# PowerSensingBoard.net
KiCad netlist of a schematic drawn in EAGLE
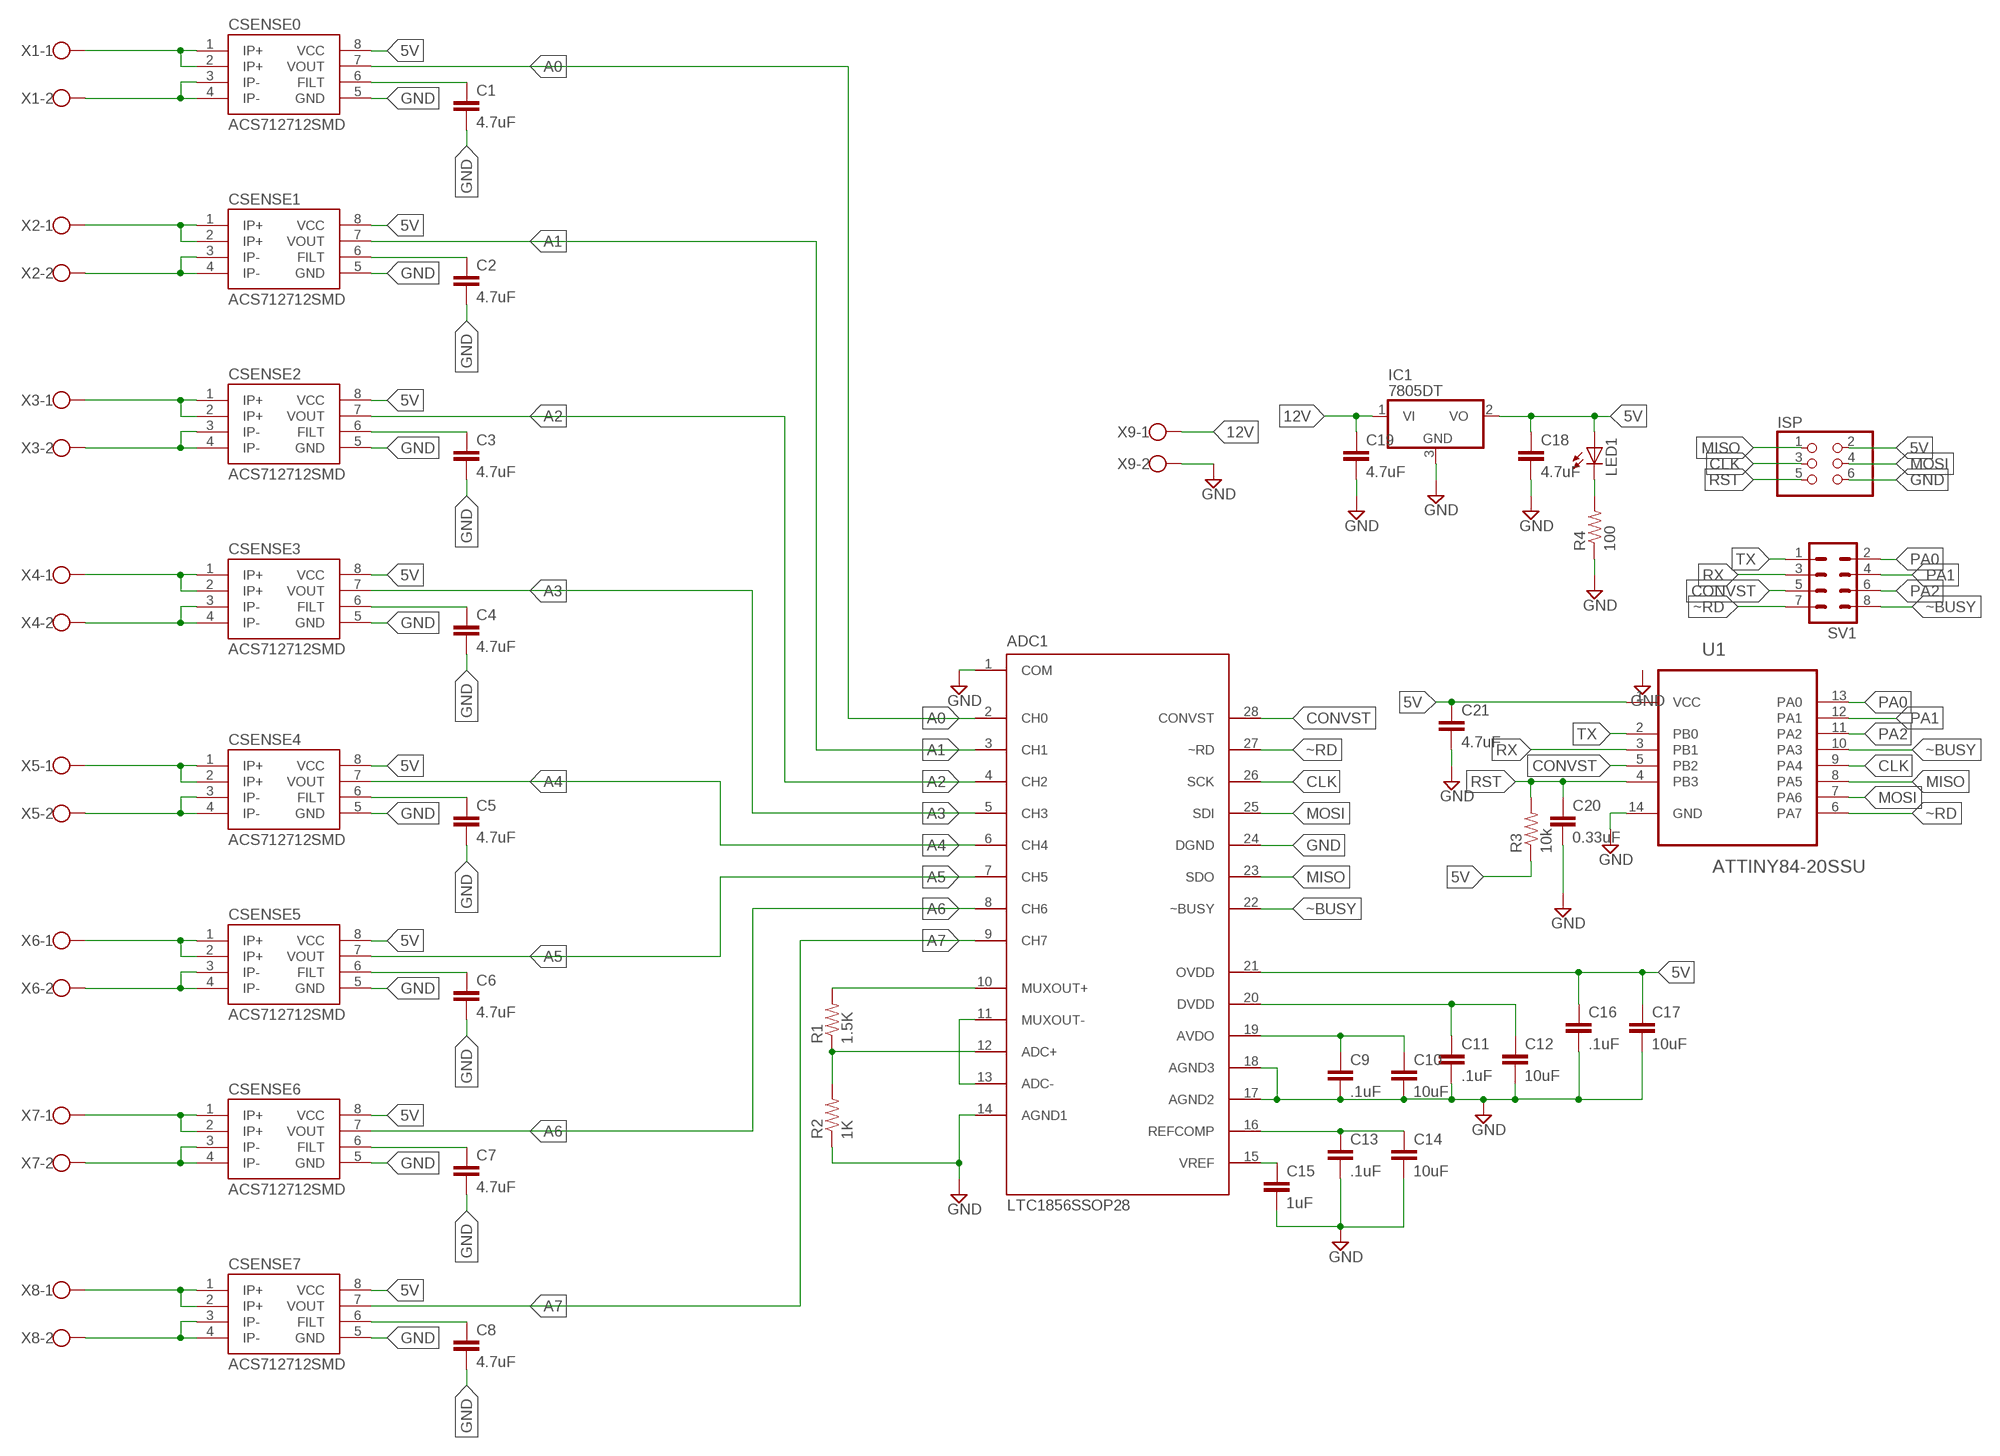
[diagram p0: schematic, sheet 1]

(export (version "E")
  (design (tool "Eeschema 10.0.6"))
  (components
    (comp (ref "ADC1")
      (value "LTC1856SSOP28")
      (footprint "eagle-import:SSOP-28")
      (libsource (lib "eagle-import") (part "LTC1856SSOP28"))
    )
    (comp (ref "C1")
      (value "4.7uF")
      (footprint "eagle-import:0603-CAP")
      (libsource (lib "eagle-import") (part "4.7UF-6.3V-10%(0603)0603"))
    )
    (comp (ref "C2")
      (value "4.7uF")
      (footprint "eagle-import:0603-CAP")
      (libsource (lib "eagle-import") (part "4.7UF-6.3V-10%(0603)0603"))
    )
    (comp (ref "C3")
      (value "4.7uF")
      (footprint "eagle-import:0603-CAP")
      (libsource (lib "eagle-import") (part "4.7UF-6.3V-10%(0603)0603"))
    )
    (comp (ref "C4")
      (value "4.7uF")
      (footprint "eagle-import:0603-CAP")
      (libsource (lib "eagle-import") (part "4.7UF-6.3V-10%(0603)0603"))
    )
    (comp (ref "C5")
      (value "4.7uF")
      (footprint "eagle-import:0603-CAP")
      (libsource (lib "eagle-import") (part "4.7UF-6.3V-10%(0603)0603"))
    )
    (comp (ref "C6")
      (value "4.7uF")
      (footprint "eagle-import:0603-CAP")
      (libsource (lib "eagle-import") (part "4.7UF-6.3V-10%(0603)0603"))
    )
    (comp (ref "C7")
      (value "4.7uF")
      (footprint "eagle-import:0603-CAP")
      (libsource (lib "eagle-import") (part "4.7UF-6.3V-10%(0603)0603"))
    )
    (comp (ref "C8")
      (value "4.7uF")
      (footprint "eagle-import:0603-CAP")
      (libsource (lib "eagle-import") (part "4.7UF-6.3V-10%(0603)0603"))
    )
    (comp (ref "C9")
      (value ".1uF")
      (footprint "eagle-import:0603-CAP")
      (libsource (lib "eagle-import") (part "4.7UF-6.3V-10%(0603)0603"))
    )
    (comp (ref "C10")
      (value "10uF")
      (footprint "eagle-import:0603-CAP")
      (libsource (lib "eagle-import") (part "4.7UF-6.3V-10%(0603)0603"))
    )
    (comp (ref "C11")
      (value ".1uF")
      (footprint "eagle-import:0603-CAP")
      (libsource (lib "eagle-import") (part "4.7UF-6.3V-10%(0603)0603"))
    )
    (comp (ref "C12")
      (value "10uF")
      (footprint "eagle-import:0603-CAP")
      (libsource (lib "eagle-import") (part "4.7UF-6.3V-10%(0603)0603"))
    )
    (comp (ref "C13")
      (value ".1uF")
      (footprint "eagle-import:0603-CAP")
      (libsource (lib "eagle-import") (part "4.7UF-6.3V-10%(0603)0603"))
    )
    (comp (ref "C14")
      (value "10uF")
      (footprint "eagle-import:0603-CAP")
      (libsource (lib "eagle-import") (part "4.7UF-6.3V-10%(0603)0603"))
    )
    (comp (ref "C15")
      (value "1uF")
      (footprint "eagle-import:0603-CAP")
      (libsource (lib "eagle-import") (part "4.7UF-6.3V-10%(0603)0603"))
    )
    (comp (ref "C16")
      (value ".1uF")
      (footprint "eagle-import:0603-CAP")
      (libsource (lib "eagle-import") (part "4.7UF-6.3V-10%(0603)0603"))
    )
    (comp (ref "C17")
      (value "10uF")
      (footprint "eagle-import:0603-CAP")
      (libsource (lib "eagle-import") (part "4.7UF-6.3V-10%(0603)0603"))
    )
    (comp (ref "C18")
      (value "4.7uF")
      (footprint "eagle-import:0603-CAP")
      (libsource (lib "eagle-import") (part "4.7UF-6.3V-10%(0603)0603"))
    )
    (comp (ref "C19")
      (value "4.7uF")
      (footprint "eagle-import:0603-CAP")
      (libsource (lib "eagle-import") (part "4.7UF-6.3V-10%(0603)0603"))
    )
    (comp (ref "C20")
      (value "0.33uF")
      (footprint "eagle-import:0805-CAP")
      (libsource (lib "eagle-import") (part "0.33UF-50V-10%(0805)"))
    )
    (comp (ref "C21")
      (value "4.7uF")
      (footprint "eagle-import:0603-CAP")
      (libsource (lib "eagle-import") (part "4.7UF-6.3V-10%(0603)0603"))
    )
    (comp (ref "CSENSE0")
      (value "ACS712712SMD")
      (footprint "eagle-import:SO08")
      (libsource (lib "eagle-import") (part "ACS712712SMD"))
    )
    (comp (ref "CSENSE1")
      (value "ACS712712SMD")
      (footprint "eagle-import:SO08")
      (libsource (lib "eagle-import") (part "ACS712712SMD"))
    )
    (comp (ref "CSENSE2")
      (value "ACS712712SMD")
      (footprint "eagle-import:SO08")
      (libsource (lib "eagle-import") (part "ACS712712SMD"))
    )
    (comp (ref "CSENSE3")
      (value "ACS712712SMD")
      (footprint "eagle-import:SO08")
      (libsource (lib "eagle-import") (part "ACS712712SMD"))
    )
    (comp (ref "CSENSE4")
      (value "ACS712712SMD")
      (footprint "eagle-import:SO08")
      (libsource (lib "eagle-import") (part "ACS712712SMD"))
    )
    (comp (ref "CSENSE5")
      (value "ACS712712SMD")
      (footprint "eagle-import:SO08")
      (libsource (lib "eagle-import") (part "ACS712712SMD"))
    )
    (comp (ref "CSENSE6")
      (value "ACS712712SMD")
      (footprint "eagle-import:SO08")
      (libsource (lib "eagle-import") (part "ACS712712SMD"))
    )
    (comp (ref "CSENSE7")
      (value "ACS712712SMD")
      (footprint "eagle-import:SO08")
      (libsource (lib "eagle-import") (part "ACS712712SMD"))
    )
    (comp (ref "IC1")
      (value "7805DT")
      (footprint "eagle-import:TO252")
      (libsource (lib "eagle-import") (part "78DT05"))
    )
    (comp (ref "ISP")
      (value "PINHD-2X3")
      (footprint "eagle-import:2X03")
      (libsource (lib "eagle-import") (part "PINHD-2X3"))
    )
    (comp (ref "LED1")
      (value "LEDCHIP-LED0805")
      (footprint "eagle-import:CHIP-LED0805")
      (libsource (lib "eagle-import") (part "LEDCHIP-LED0805"))
    )
    (comp (ref "R1")
      (value "1.5K")
      (footprint "eagle-import:0603-RES")
      (libsource (lib "eagle-import") (part "1KOHM-1/10W-1%(0603)"))
    )
    (comp (ref "R2")
      (value "1K")
      (footprint "eagle-import:0603-RES")
      (libsource (lib "eagle-import") (part "1KOHM-1/10W-1%(0603)"))
    )
    (comp (ref "R3")
      (value "10k")
      (footprint "eagle-import:0805")
      (libsource (lib "eagle-import") (part "0.3OHM-1/8W-1%(0805)"))
    )
    (comp (ref "R4")
      (value "100")
      (footprint "eagle-import:0603-RES")
      (libsource (lib "eagle-import") (part "1KOHM-1/10W-1%(0603)"))
    )
    (comp (ref "SV1")
      (value "MA04-2")
      (footprint "eagle-import:MA04-2")
      (libsource (lib "eagle-import") (part "MA04-2"))
    )
    (comp (ref "U1")
      (value "ATTINY84-20SSU")
      (footprint "eagle-import:SOIC127P600X175-14N")
      (libsource (lib "eagle-import") (part "ATTINY84-20SSU"))
    )
    (comp (ref "X1")
      (value "W237-102")
      (footprint "eagle-import:W237-102")
      (fields (field (name "MPN") "237-102"))
      (libsource (lib "eagle-import") (part "W237-102"))
    )
    (comp (ref "X2")
      (value "W237-102")
      (footprint "eagle-import:W237-102")
      (fields (field (name "MPN") "237-102"))
      (libsource (lib "eagle-import") (part "W237-102"))
    )
    (comp (ref "X3")
      (value "W237-102")
      (footprint "eagle-import:W237-102")
      (fields (field (name "MPN") "237-102"))
      (libsource (lib "eagle-import") (part "W237-102"))
    )
    (comp (ref "X4")
      (value "W237-102")
      (footprint "eagle-import:W237-102")
      (fields (field (name "MPN") "237-102"))
      (libsource (lib "eagle-import") (part "W237-102"))
    )
    (comp (ref "X5")
      (value "W237-102")
      (footprint "eagle-import:W237-102")
      (fields (field (name "MPN") "237-102"))
      (libsource (lib "eagle-import") (part "W237-102"))
    )
    (comp (ref "X6")
      (value "W237-102")
      (footprint "eagle-import:W237-102")
      (fields (field (name "MPN") "237-102"))
      (libsource (lib "eagle-import") (part "W237-102"))
    )
    (comp (ref "X7")
      (value "W237-102")
      (footprint "eagle-import:W237-102")
      (fields (field (name "MPN") "237-102"))
      (libsource (lib "eagle-import") (part "W237-102"))
    )
    (comp (ref "X8")
      (value "W237-102")
      (footprint "eagle-import:W237-102")
      (fields (field (name "MPN") "237-102"))
      (libsource (lib "eagle-import") (part "W237-102"))
    )
    (comp (ref "X9")
      (value "W237-102")
      (footprint "eagle-import:W237-102")
      (fields (field (name "MPN") "237-102"))
      (libsource (lib "eagle-import") (part "W237-102"))
    )
  )
  (nets
    (net (code "1") (name "/~{BUSY}") (class "Default")
      (node (ref "ADC1") (pin "22") (pinfunction "~{BUSY}_22") (pintype "bidirectional"))
      (node (ref "SV1") (pin "8") (pinfunction "8_8") (pintype "passive"))
      (node (ref "U1") (pin "10") (pinfunction "PA3_10") (pintype "bidirectional"))
    )
    (net (code "2") (name "/~{RD}") (class "Default")
      (node (ref "ADC1") (pin "27") (pinfunction "~{RD}_27") (pintype "bidirectional"))
      (node (ref "SV1") (pin "7") (pinfunction "7_7") (pintype "passive"))
      (node (ref "U1") (pin "6") (pinfunction "PA7_6") (pintype "bidirectional"))
    )
    (net (code "3") (name "5V") (class "Default")
      (node (ref "ADC1") (pin "21") (pinfunction "OVDD_21") (pintype "bidirectional"))
      (node (ref "C16") (pin "1") (pinfunction "1_1") (pintype "passive"))
      (node (ref "C17") (pin "1") (pinfunction "1_1") (pintype "passive"))
      (node (ref "C18") (pin "1") (pinfunction "1_1") (pintype "passive"))
      (node (ref "C21") (pin "1") (pinfunction "1_1") (pintype "passive"))
      (node (ref "CSENSE0") (pin "8") (pinfunction "VCC_8") (pintype "bidirectional"))
      (node (ref "CSENSE1") (pin "8") (pinfunction "VCC_8") (pintype "bidirectional"))
      (node (ref "CSENSE2") (pin "8") (pinfunction "VCC_8") (pintype "bidirectional"))
      (node (ref "CSENSE3") (pin "8") (pinfunction "VCC_8") (pintype "bidirectional"))
      (node (ref "CSENSE4") (pin "8") (pinfunction "VCC_8") (pintype "bidirectional"))
      (node (ref "CSENSE5") (pin "8") (pinfunction "VCC_8") (pintype "bidirectional"))
      (node (ref "CSENSE6") (pin "8") (pinfunction "VCC_8") (pintype "bidirectional"))
      (node (ref "CSENSE7") (pin "8") (pinfunction "VCC_8") (pintype "bidirectional"))
      (node (ref "IC1") (pin "2") (pinfunction "VO_2") (pintype "passive"))
      (node (ref "ISP") (pin "2") (pinfunction "2_2") (pintype "passive"))
      (node (ref "LED1") (pin "A") (pinfunction "A_A") (pintype "passive"))
      (node (ref "R3") (pin "1") (pinfunction "1_1") (pintype "passive"))
      (node (ref "U1") (pin "1") (pinfunction "VCC_1") (pintype "power_in"))
    )
    (net (code "4") (name "12V") (class "Default")
      (node (ref "C19") (pin "1") (pinfunction "1_1") (pintype "passive"))
      (node (ref "IC1") (pin "1") (pinfunction "VI_1") (pintype "input"))
      (node (ref "X9") (pin "1") (pinfunction "KL_1") (pintype "passive"))
    )
    (net (code "5") (name "A0") (class "Default")
      (node (ref "ADC1") (pin "2") (pinfunction "CH0_2") (pintype "bidirectional"))
      (node (ref "CSENSE0") (pin "7") (pinfunction "VOUT_7") (pintype "bidirectional"))
    )
    (net (code "6") (name "A1") (class "Default")
      (node (ref "ADC1") (pin "3") (pinfunction "CH1_3") (pintype "bidirectional"))
      (node (ref "CSENSE1") (pin "7") (pinfunction "VOUT_7") (pintype "bidirectional"))
    )
    (net (code "7") (name "A2") (class "Default")
      (node (ref "ADC1") (pin "4") (pinfunction "CH2_4") (pintype "bidirectional"))
      (node (ref "CSENSE2") (pin "7") (pinfunction "VOUT_7") (pintype "bidirectional"))
    )
    (net (code "8") (name "A3") (class "Default")
      (node (ref "ADC1") (pin "5") (pinfunction "CH3_5") (pintype "bidirectional"))
      (node (ref "CSENSE3") (pin "7") (pinfunction "VOUT_7") (pintype "bidirectional"))
    )
    (net (code "9") (name "A4") (class "Default")
      (node (ref "ADC1") (pin "6") (pinfunction "CH4_6") (pintype "bidirectional"))
      (node (ref "CSENSE4") (pin "7") (pinfunction "VOUT_7") (pintype "bidirectional"))
    )
    (net (code "10") (name "A5") (class "Default")
      (node (ref "ADC1") (pin "7") (pinfunction "CH5_7") (pintype "bidirectional"))
      (node (ref "CSENSE5") (pin "7") (pinfunction "VOUT_7") (pintype "bidirectional"))
    )
    (net (code "11") (name "A6") (class "Default")
      (node (ref "ADC1") (pin "8") (pinfunction "CH6_8") (pintype "bidirectional"))
      (node (ref "CSENSE6") (pin "7") (pinfunction "VOUT_7") (pintype "bidirectional"))
    )
    (net (code "12") (name "A7") (class "Default")
      (node (ref "ADC1") (pin "9") (pinfunction "CH7_9") (pintype "bidirectional"))
      (node (ref "CSENSE7") (pin "7") (pinfunction "VOUT_7") (pintype "bidirectional"))
    )
    (net (code "13") (name "CLK") (class "Default")
      (node (ref "ADC1") (pin "26") (pinfunction "SCK_26") (pintype "bidirectional"))
      (node (ref "ISP") (pin "3") (pinfunction "3_3") (pintype "passive"))
      (node (ref "U1") (pin "9") (pinfunction "PA4_9") (pintype "bidirectional"))
    )
    (net (code "14") (name "CONVST") (class "Default")
      (node (ref "ADC1") (pin "28") (pinfunction "CONVST_28") (pintype "bidirectional"))
      (node (ref "SV1") (pin "5") (pinfunction "5_5") (pintype "passive"))
      (node (ref "U1") (pin "5") (pinfunction "PB2_5") (pintype "bidirectional"))
    )
    (net (code "15") (name "GND") (class "Default")
      (node (ref "ADC1") (pin "1") (pinfunction "COM_1") (pintype "bidirectional"))
      (node (ref "ADC1") (pin "14") (pinfunction "AGND1_14") (pintype "bidirectional"))
      (node (ref "ADC1") (pin "17") (pinfunction "AGND2_17") (pintype "bidirectional"))
      (node (ref "ADC1") (pin "18") (pinfunction "AGND3_18") (pintype "bidirectional"))
      (node (ref "ADC1") (pin "24") (pinfunction "DGND_24") (pintype "bidirectional"))
      (node (ref "C1") (pin "2") (pinfunction "2_2") (pintype "passive"))
      (node (ref "C10") (pin "2") (pinfunction "2_2") (pintype "passive"))
      (node (ref "C11") (pin "2") (pinfunction "2_2") (pintype "passive"))
      (node (ref "C12") (pin "2") (pinfunction "2_2") (pintype "passive"))
      (node (ref "C13") (pin "2") (pinfunction "2_2") (pintype "passive"))
      (node (ref "C14") (pin "2") (pinfunction "2_2") (pintype "passive"))
      (node (ref "C15") (pin "2") (pinfunction "2_2") (pintype "passive"))
      (node (ref "C16") (pin "2") (pinfunction "2_2") (pintype "passive"))
      (node (ref "C17") (pin "2") (pinfunction "2_2") (pintype "passive"))
      (node (ref "C18") (pin "2") (pinfunction "2_2") (pintype "passive"))
      (node (ref "C19") (pin "2") (pinfunction "2_2") (pintype "passive"))
      (node (ref "C2") (pin "2") (pinfunction "2_2") (pintype "passive"))
      (node (ref "C20") (pin "2") (pinfunction "2_2") (pintype "passive"))
      (node (ref "C21") (pin "2") (pinfunction "2_2") (pintype "passive"))
      (node (ref "C3") (pin "2") (pinfunction "2_2") (pintype "passive"))
      (node (ref "C4") (pin "2") (pinfunction "2_2") (pintype "passive"))
      (node (ref "C5") (pin "2") (pinfunction "2_2") (pintype "passive"))
      (node (ref "C6") (pin "2") (pinfunction "2_2") (pintype "passive"))
      (node (ref "C7") (pin "2") (pinfunction "2_2") (pintype "passive"))
      (node (ref "C8") (pin "2") (pinfunction "2_2") (pintype "passive"))
      (node (ref "C9") (pin "2") (pinfunction "2_2") (pintype "passive"))
      (node (ref "CSENSE0") (pin "5") (pinfunction "GND_5") (pintype "bidirectional"))
      (node (ref "CSENSE1") (pin "5") (pinfunction "GND_5") (pintype "bidirectional"))
      (node (ref "CSENSE2") (pin "5") (pinfunction "GND_5") (pintype "bidirectional"))
      (node (ref "CSENSE3") (pin "5") (pinfunction "GND_5") (pintype "bidirectional"))
      (node (ref "CSENSE4") (pin "5") (pinfunction "GND_5") (pintype "bidirectional"))
      (node (ref "CSENSE5") (pin "5") (pinfunction "GND_5") (pintype "bidirectional"))
      (node (ref "CSENSE6") (pin "5") (pinfunction "GND_5") (pintype "bidirectional"))
      (node (ref "CSENSE7") (pin "5") (pinfunction "GND_5") (pintype "bidirectional"))
      (node (ref "IC1") (pin "3") (pinfunction "GND_3") (pintype "passive"))
      (node (ref "ISP") (pin "6") (pinfunction "6_6") (pintype "passive"))
      (node (ref "R2") (pin "1") (pinfunction "1_1") (pintype "passive"))
      (node (ref "R4") (pin "1") (pinfunction "1_1") (pintype "passive"))
      (node (ref "U1") (pin "14") (pinfunction "GND_14") (pintype "passive"))
      (node (ref "X9") (pin "2") (pinfunction "KL_2") (pintype "passive"))
    )
    (net (code "16") (name "MISO") (class "Default")
      (node (ref "ADC1") (pin "23") (pinfunction "SDO_23") (pintype "bidirectional"))
      (node (ref "ISP") (pin "1") (pinfunction "1_1") (pintype "passive"))
      (node (ref "U1") (pin "8") (pinfunction "PA5_8") (pintype "bidirectional"))
    )
    (net (code "17") (name "MOSI") (class "Default")
      (node (ref "ADC1") (pin "25") (pinfunction "SDI_25") (pintype "bidirectional"))
      (node (ref "ISP") (pin "4") (pinfunction "4_4") (pintype "passive"))
      (node (ref "U1") (pin "7") (pinfunction "PA6_7") (pintype "bidirectional"))
    )
    (net (code "18") (name "Net-(ADC1-ADC+)") (class "Default")
      (node (ref "ADC1") (pin "12") (pinfunction "ADC+_12") (pintype "bidirectional"))
      (node (ref "R1") (pin "1") (pinfunction "1_1") (pintype "passive"))
      (node (ref "R2") (pin "2") (pinfunction "2_2") (pintype "passive"))
    )
    (net (code "19") (name "Net-(ADC1-ADC-)") (class "Default")
      (node (ref "ADC1") (pin "11") (pinfunction "MUXOUT-_11") (pintype "bidirectional"))
      (node (ref "ADC1") (pin "13") (pinfunction "ADC-_13") (pintype "bidirectional"))
    )
    (net (code "20") (name "Net-(ADC1-AVDO)") (class "Default")
      (node (ref "ADC1") (pin "19") (pinfunction "AVDO_19") (pintype "bidirectional"))
      (node (ref "C10") (pin "1") (pinfunction "1_1") (pintype "passive"))
      (node (ref "C9") (pin "1") (pinfunction "1_1") (pintype "passive"))
    )
    (net (code "21") (name "Net-(ADC1-DVDD)") (class "Default")
      (node (ref "ADC1") (pin "20") (pinfunction "DVDD_20") (pintype "bidirectional"))
      (node (ref "C11") (pin "1") (pinfunction "1_1") (pintype "passive"))
      (node (ref "C12") (pin "1") (pinfunction "1_1") (pintype "passive"))
    )
    (net (code "22") (name "Net-(ADC1-MUXOUT+)") (class "Default")
      (node (ref "ADC1") (pin "10") (pinfunction "MUXOUT+_10") (pintype "bidirectional"))
      (node (ref "R1") (pin "2") (pinfunction "2_2") (pintype "passive"))
    )
    (net (code "23") (name "Net-(ADC1-REFCOMP)") (class "Default")
      (node (ref "ADC1") (pin "16") (pinfunction "REFCOMP_16") (pintype "bidirectional"))
      (node (ref "C13") (pin "1") (pinfunction "1_1") (pintype "passive"))
      (node (ref "C14") (pin "1") (pinfunction "1_1") (pintype "passive"))
    )
    (net (code "24") (name "Net-(ADC1-VREF)") (class "Default")
      (node (ref "ADC1") (pin "15") (pinfunction "VREF_15") (pintype "bidirectional"))
      (node (ref "C15") (pin "1") (pinfunction "1_1") (pintype "passive"))
    )
    (net (code "25") (name "Net-(CSENSE0-FILT)") (class "Default")
      (node (ref "C1") (pin "1") (pinfunction "1_1") (pintype "passive"))
      (node (ref "CSENSE0") (pin "6") (pinfunction "FILT_6") (pintype "bidirectional"))
    )
    (net (code "26") (name "Net-(CSENSE1-FILT)") (class "Default")
      (node (ref "C2") (pin "1") (pinfunction "1_1") (pintype "passive"))
      (node (ref "CSENSE1") (pin "6") (pinfunction "FILT_6") (pintype "bidirectional"))
    )
    (net (code "27") (name "Net-(CSENSE2-FILT)") (class "Default")
      (node (ref "C3") (pin "1") (pinfunction "1_1") (pintype "passive"))
      (node (ref "CSENSE2") (pin "6") (pinfunction "FILT_6") (pintype "bidirectional"))
    )
    (net (code "28") (name "Net-(CSENSE3-FILT)") (class "Default")
      (node (ref "C4") (pin "1") (pinfunction "1_1") (pintype "passive"))
      (node (ref "CSENSE3") (pin "6") (pinfunction "FILT_6") (pintype "bidirectional"))
    )
    (net (code "29") (name "Net-(CSENSE4-FILT)") (class "Default")
      (node (ref "C5") (pin "1") (pinfunction "1_1") (pintype "passive"))
      (node (ref "CSENSE4") (pin "6") (pinfunction "FILT_6") (pintype "bidirectional"))
    )
    (net (code "30") (name "Net-(CSENSE5-FILT)") (class "Default")
      (node (ref "C6") (pin "1") (pinfunction "1_1") (pintype "passive"))
      (node (ref "CSENSE5") (pin "6") (pinfunction "FILT_6") (pintype "bidirectional"))
    )
    (net (code "31") (name "Net-(CSENSE6-FILT)") (class "Default")
      (node (ref "C7") (pin "1") (pinfunction "1_1") (pintype "passive"))
      (node (ref "CSENSE6") (pin "6") (pinfunction "FILT_6") (pintype "bidirectional"))
    )
    (net (code "32") (name "Net-(CSENSE7-FILT)") (class "Default")
      (node (ref "C8") (pin "1") (pinfunction "1_1") (pintype "passive"))
      (node (ref "CSENSE7") (pin "6") (pinfunction "FILT_6") (pintype "bidirectional"))
    )
    (net (code "33") (name "Net-(LED1-PadC)") (class "Default")
      (node (ref "LED1") (pin "C") (pinfunction "C_C") (pintype "passive"))
      (node (ref "R4") (pin "2") (pinfunction "2_2") (pintype "passive"))
    )
    (net (code "34") (name "Net-(X1A-KL)") (class "Default")
      (node (ref "CSENSE0") (pin "1") (pinfunction "IP+_1") (pintype "bidirectional"))
      (node (ref "CSENSE0") (pin "2") (pinfunction "IP+_2") (pintype "bidirectional"))
      (node (ref "X1") (pin "1") (pinfunction "KL_1") (pintype "passive"))
    )
    (net (code "35") (name "Net-(X1B-KL)") (class "Default")
      (node (ref "CSENSE0") (pin "3") (pinfunction "IP-_3") (pintype "bidirectional"))
      (node (ref "CSENSE0") (pin "4") (pinfunction "IP-_4") (pintype "bidirectional"))
      (node (ref "X1") (pin "2") (pinfunction "KL_2") (pintype "passive"))
    )
    (net (code "36") (name "Net-(X2A-KL)") (class "Default")
      (node (ref "CSENSE1") (pin "1") (pinfunction "IP+_1") (pintype "bidirectional"))
      (node (ref "CSENSE1") (pin "2") (pinfunction "IP+_2") (pintype "bidirectional"))
      (node (ref "X2") (pin "1") (pinfunction "KL_1") (pintype "passive"))
    )
    (net (code "37") (name "Net-(X2B-KL)") (class "Default")
      (node (ref "CSENSE1") (pin "3") (pinfunction "IP-_3") (pintype "bidirectional"))
      (node (ref "CSENSE1") (pin "4") (pinfunction "IP-_4") (pintype "bidirectional"))
      (node (ref "X2") (pin "2") (pinfunction "KL_2") (pintype "passive"))
    )
    (net (code "38") (name "Net-(X3A-KL)") (class "Default")
      (node (ref "CSENSE2") (pin "1") (pinfunction "IP+_1") (pintype "bidirectional"))
      (node (ref "CSENSE2") (pin "2") (pinfunction "IP+_2") (pintype "bidirectional"))
      (node (ref "X3") (pin "1") (pinfunction "KL_1") (pintype "passive"))
    )
    (net (code "39") (name "Net-(X3B-KL)") (class "Default")
      (node (ref "CSENSE2") (pin "3") (pinfunction "IP-_3") (pintype "bidirectional"))
      (node (ref "CSENSE2") (pin "4") (pinfunction "IP-_4") (pintype "bidirectional"))
      (node (ref "X3") (pin "2") (pinfunction "KL_2") (pintype "passive"))
    )
    (net (code "40") (name "Net-(X4A-KL)") (class "Default")
      (node (ref "CSENSE3") (pin "1") (pinfunction "IP+_1") (pintype "bidirectional"))
      (node (ref "CSENSE3") (pin "2") (pinfunction "IP+_2") (pintype "bidirectional"))
      (node (ref "X4") (pin "1") (pinfunction "KL_1") (pintype "passive"))
    )
    (net (code "41") (name "Net-(X4B-KL)") (class "Default")
      (node (ref "CSENSE3") (pin "3") (pinfunction "IP-_3") (pintype "bidirectional"))
      (node (ref "CSENSE3") (pin "4") (pinfunction "IP-_4") (pintype "bidirectional"))
      (node (ref "X4") (pin "2") (pinfunction "KL_2") (pintype "passive"))
    )
    (net (code "42") (name "Net-(X5A-KL)") (class "Default")
      (node (ref "CSENSE4") (pin "1") (pinfunction "IP+_1") (pintype "bidirectional"))
      (node (ref "CSENSE4") (pin "2") (pinfunction "IP+_2") (pintype "bidirectional"))
      (node (ref "X5") (pin "1") (pinfunction "KL_1") (pintype "passive"))
    )
    (net (code "43") (name "Net-(X5B-KL)") (class "Default")
      (node (ref "CSENSE4") (pin "3") (pinfunction "IP-_3") (pintype "bidirectional"))
      (node (ref "CSENSE4") (pin "4") (pinfunction "IP-_4") (pintype "bidirectional"))
      (node (ref "X5") (pin "2") (pinfunction "KL_2") (pintype "passive"))
    )
    (net (code "44") (name "Net-(X6A-KL)") (class "Default")
      (node (ref "CSENSE5") (pin "1") (pinfunction "IP+_1") (pintype "bidirectional"))
      (node (ref "CSENSE5") (pin "2") (pinfunction "IP+_2") (pintype "bidirectional"))
      (node (ref "X6") (pin "1") (pinfunction "KL_1") (pintype "passive"))
    )
    (net (code "45") (name "Net-(X6B-KL)") (class "Default")
      (node (ref "CSENSE5") (pin "3") (pinfunction "IP-_3") (pintype "bidirectional"))
      (node (ref "CSENSE5") (pin "4") (pinfunction "IP-_4") (pintype "bidirectional"))
      (node (ref "X6") (pin "2") (pinfunction "KL_2") (pintype "passive"))
    )
    (net (code "46") (name "Net-(X7A-KL)") (class "Default")
      (node (ref "CSENSE6") (pin "1") (pinfunction "IP+_1") (pintype "bidirectional"))
      (node (ref "CSENSE6") (pin "2") (pinfunction "IP+_2") (pintype "bidirectional"))
      (node (ref "X7") (pin "1") (pinfunction "KL_1") (pintype "passive"))
    )
    (net (code "47") (name "Net-(X7B-KL)") (class "Default")
      (node (ref "CSENSE6") (pin "3") (pinfunction "IP-_3") (pintype "bidirectional"))
      (node (ref "CSENSE6") (pin "4") (pinfunction "IP-_4") (pintype "bidirectional"))
      (node (ref "X7") (pin "2") (pinfunction "KL_2") (pintype "passive"))
    )
    (net (code "48") (name "Net-(X8A-KL)") (class "Default")
      (node (ref "CSENSE7") (pin "1") (pinfunction "IP+_1") (pintype "bidirectional"))
      (node (ref "CSENSE7") (pin "2") (pinfunction "IP+_2") (pintype "bidirectional"))
      (node (ref "X8") (pin "1") (pinfunction "KL_1") (pintype "passive"))
    )
    (net (code "49") (name "Net-(X8B-KL)") (class "Default")
      (node (ref "CSENSE7") (pin "3") (pinfunction "IP-_3") (pintype "bidirectional"))
      (node (ref "CSENSE7") (pin "4") (pinfunction "IP-_4") (pintype "bidirectional"))
      (node (ref "X8") (pin "2") (pinfunction "KL_2") (pintype "passive"))
    )
    (net (code "50") (name "PA0") (class "Default")
      (node (ref "SV1") (pin "2") (pinfunction "2_2") (pintype "passive"))
      (node (ref "U1") (pin "13") (pinfunction "PA0_13") (pintype "bidirectional"))
    )
    (net (code "51") (name "PA1") (class "Default")
      (node (ref "SV1") (pin "4") (pinfunction "4_4") (pintype "passive"))
      (node (ref "U1") (pin "12") (pinfunction "PA1_12") (pintype "bidirectional"))
    )
    (net (code "52") (name "PA2") (class "Default")
      (node (ref "SV1") (pin "6") (pinfunction "6_6") (pintype "passive"))
      (node (ref "U1") (pin "11") (pinfunction "PA2_11") (pintype "bidirectional"))
    )
    (net (code "53") (name "RST") (class "Default")
      (node (ref "C20") (pin "1") (pinfunction "1_1") (pintype "passive"))
      (node (ref "ISP") (pin "5") (pinfunction "5_5") (pintype "passive"))
      (node (ref "R3") (pin "2") (pinfunction "2_2") (pintype "passive"))
      (node (ref "U1") (pin "4") (pinfunction "PB3_4") (pintype "bidirectional"))
    )
    (net (code "54") (name "RX") (class "Default")
      (node (ref "SV1") (pin "3") (pinfunction "3_3") (pintype "passive"))
      (node (ref "U1") (pin "3") (pinfunction "PB1_3") (pintype "bidirectional"))
    )
    (net (code "55") (name "TX") (class "Default")
      (node (ref "SV1") (pin "1") (pinfunction "1_1") (pintype "passive"))
      (node (ref "U1") (pin "2") (pinfunction "PB0_2") (pintype "bidirectional"))
    )
  )
)
